# Sensor.net
KiCad netlist of a schematic drawn in Altium Designer
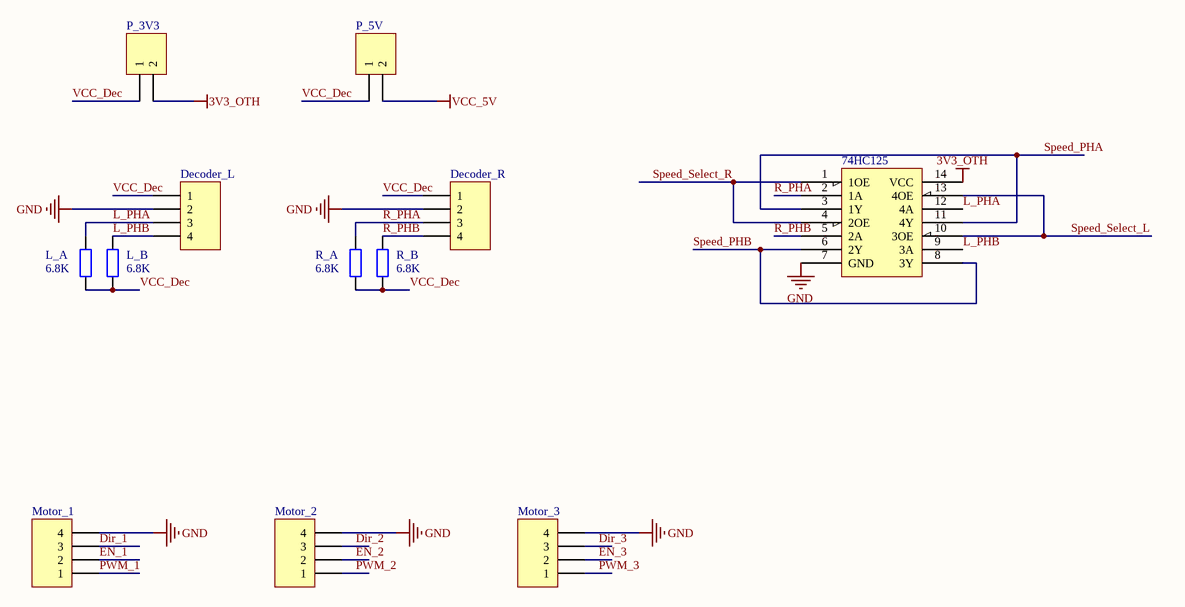
[diagram p0: Sensor.SchDoc]

(export (version "E")
  (design (tool "Eeschema 10.0.6"))
  (components
    (comp (ref "74HC125") (value "74HC125") (footprint "751A-02_N") (libsource (lib "mine") (part "74HC125")))
    (comp (ref "Decoder_L")
      (value "Header 4")
      (footprint "HDR1X4")
      (description "Header, 4-Pin")
      (fields (field (name "PUBLISHER") "Altium Limited"))
      (libsource (lib "") (part "Header 4_1"))
    )
    (comp (ref "Decoder_R")
      (value "Header 4")
      (footprint "HDR1X4")
      (description "Header, 4-Pin")
      (fields (field (name "PUBLISHER") "Altium Limited"))
      (libsource (lib "") (part "Header 4_1"))
    )
    (comp (ref "L_A")
      (value "6.8K")
      (footprint "0805-S")
      (description "Resistor")
      (fields (field (name "PUBLISHER") "Altium Limited"))
      (libsource (lib "lichao_Library") (part "Res2_3"))
    )
    (comp (ref "L_B")
      (value "6.8K")
      (footprint "0805-S")
      (description "Resistor")
      (fields (field (name "PUBLISHER") "Altium Limited"))
      (libsource (lib "lichao_Library") (part "Res2_3"))
    )
    (comp (ref "Motor_1")
      (value "Header 4")
      (footprint "HDR1X4")
      (description "Header, 4-Pin")
      (fields (field (name "PUBLISHER") "Altium Limited"))
      (libsource (lib "Miscellaneous Connectors") (part "Header 4"))
    )
    (comp (ref "Motor_2")
      (value "Header 4")
      (footprint "HDR1X4")
      (description "Header, 4-Pin")
      (fields (field (name "PUBLISHER") "Altium Limited"))
      (libsource (lib "Miscellaneous Connectors") (part "Header 4"))
    )
    (comp (ref "Motor_3")
      (value "Header 4")
      (footprint "HDR1X4")
      (description "Header, 4-Pin")
      (fields (field (name "PUBLISHER") "Altium Limited"))
      (libsource (lib "Miscellaneous Connectors") (part "Header 4"))
    )
    (comp (ref "P_3V3")
      (value "Header 2")
      (footprint "HDR1X2")
      (description "Header, 2-Pin")
      (fields (field (name "PUBLISHER") "Altium Limited"))
      (libsource (lib "Miscellaneous Connectors") (part "Header 2"))
    )
    (comp (ref "P_5V")
      (value "Header 2")
      (footprint "HDR1X2")
      (description "Header, 2-Pin")
      (fields (field (name "PUBLISHER") "Altium Limited"))
      (libsource (lib "Miscellaneous Connectors") (part "Header 2"))
    )
    (comp (ref "R_A")
      (value "6.8K")
      (footprint "0805-S")
      (description "Resistor")
      (fields (field (name "PUBLISHER") "Altium Limited"))
      (libsource (lib "lichao_Library") (part "Res2_3"))
    )
    (comp (ref "R_B")
      (value "6.8K")
      (footprint "0805-S")
      (description "Resistor")
      (fields (field (name "PUBLISHER") "Altium Limited"))
      (libsource (lib "lichao_Library") (part "Res2_3"))
    )
  )
  (nets
    (net (code "1") (name "/Dir_1") (class "Default")
      (node (ref "Motor_1") (pin "3") (pinfunction "3_3") (pintype "passive"))
    )
    (net (code "2") (name "/Dir_2") (class "Default")
      (node (ref "Motor_2") (pin "3") (pinfunction "3_3") (pintype "passive"))
    )
    (net (code "3") (name "/Dir_3") (class "Default")
      (node (ref "Motor_3") (pin "3") (pinfunction "3_3") (pintype "passive"))
    )
    (net (code "4") (name "/EN_1") (class "Default")
      (node (ref "Motor_1") (pin "2") (pinfunction "2_2") (pintype "passive"))
    )
    (net (code "5") (name "/EN_2") (class "Default")
      (node (ref "Motor_2") (pin "2") (pinfunction "2_2") (pintype "passive"))
    )
    (net (code "6") (name "/EN_3") (class "Default")
      (node (ref "Motor_3") (pin "2") (pinfunction "2_2") (pintype "passive"))
    )
    (net (code "7") (name "/L_PHA") (class "Default")
      (node (ref "74HC125") (pin "12") (pinfunction "4A_12") (pintype "passive"))
      (node (ref "Decoder_L") (pin "3") (pinfunction "3_3") (pintype "passive"))
      (node (ref "L_A") (pin "2") (pinfunction "2_2") (pintype "passive"))
    )
    (net (code "8") (name "/L_PHB") (class "Default")
      (node (ref "74HC125") (pin "9") (pinfunction "3A_9") (pintype "passive"))
      (node (ref "Decoder_L") (pin "4") (pinfunction "4_4") (pintype "passive"))
      (node (ref "L_B") (pin "2") (pinfunction "2_2") (pintype "passive"))
    )
    (net (code "9") (name "/PWM_1") (class "Default")
      (node (ref "Motor_1") (pin "1") (pinfunction "1_1") (pintype "passive"))
    )
    (net (code "10") (name "/PWM_2") (class "Default")
      (node (ref "Motor_2") (pin "1") (pinfunction "1_1") (pintype "passive"))
    )
    (net (code "11") (name "/PWM_3") (class "Default")
      (node (ref "Motor_3") (pin "1") (pinfunction "1_1") (pintype "passive"))
    )
    (net (code "12") (name "/R_PHA") (class "Default")
      (node (ref "74HC125") (pin "2") (pinfunction "1A_2") (pintype "passive"))
      (node (ref "Decoder_R") (pin "3") (pinfunction "3_3") (pintype "passive"))
      (node (ref "R_A") (pin "2") (pinfunction "2_2") (pintype "passive"))
    )
    (net (code "13") (name "/R_PHB") (class "Default")
      (node (ref "74HC125") (pin "5") (pinfunction "2A_5") (pintype "passive"))
      (node (ref "Decoder_R") (pin "4") (pinfunction "4_4") (pintype "passive"))
      (node (ref "R_B") (pin "2") (pinfunction "2_2") (pintype "passive"))
    )
    (net (code "14") (name "/Speed_PHA") (class "Default")
      (node (ref "74HC125") (pin "11") (pinfunction "4Y_11") (pintype "passive"))
      (node (ref "74HC125") (pin "3") (pinfunction "1Y_3") (pintype "passive"))
    )
    (net (code "15") (name "/Speed_PHB") (class "Default")
      (node (ref "74HC125") (pin "6") (pinfunction "2Y_6") (pintype "passive"))
      (node (ref "74HC125") (pin "8") (pinfunction "3Y_8") (pintype "passive"))
    )
    (net (code "16") (name "/Speed_Select_L") (class "Default")
      (node (ref "74HC125") (pin "10") (pinfunction "3OE_10") (pintype "passive"))
      (node (ref "74HC125") (pin "13") (pinfunction "4OE_13") (pintype "passive"))
    )
    (net (code "17") (name "/Speed_Select_R") (class "Default")
      (node (ref "74HC125") (pin "1") (pinfunction "1OE_1") (pintype "passive"))
      (node (ref "74HC125") (pin "4") (pinfunction "2OE_4") (pintype "passive"))
    )
    (net (code "18") (name "/VCC_Dec") (class "Default")
      (node (ref "Decoder_L") (pin "1") (pinfunction "1_1") (pintype "passive"))
      (node (ref "Decoder_R") (pin "1") (pinfunction "1_1") (pintype "passive"))
      (node (ref "L_A") (pin "1") (pinfunction "1_1") (pintype "passive"))
      (node (ref "L_B") (pin "1") (pinfunction "1_1") (pintype "passive"))
      (node (ref "P_3V3") (pin "1") (pinfunction "1_1") (pintype "passive"))
      (node (ref "P_5V") (pin "1") (pinfunction "1_1") (pintype "passive"))
      (node (ref "R_A") (pin "1") (pinfunction "1_1") (pintype "passive"))
      (node (ref "R_B") (pin "1") (pinfunction "1_1") (pintype "passive"))
    )
    (net (code "19") (name "3V3_OTH") (class "Default")
      (node (ref "74HC125") (pin "14") (pinfunction "VCC_14") (pintype "passive"))
      (node (ref "P_3V3") (pin "2") (pinfunction "2_2") (pintype "passive"))
    )
    (net (code "20") (name "GND") (class "Default")
      (node (ref "74HC125") (pin "7") (pinfunction "GND_7") (pintype "passive"))
      (node (ref "Decoder_L") (pin "2") (pinfunction "2_2") (pintype "passive"))
      (node (ref "Decoder_R") (pin "2") (pinfunction "2_2") (pintype "passive"))
      (node (ref "Motor_1") (pin "4") (pinfunction "4_4") (pintype "passive"))
      (node (ref "Motor_2") (pin "4") (pinfunction "4_4") (pintype "passive"))
      (node (ref "Motor_3") (pin "4") (pinfunction "4_4") (pintype "passive"))
    )
    (net (code "21") (name "VCC_5V") (class "Default")
      (node (ref "P_5V") (pin "2") (pinfunction "2_2") (pintype "passive"))
    )
  )
)
